# QCopterCAM_LED_Sch.net
KiCad netlist of a schematic drawn in Altium Designer
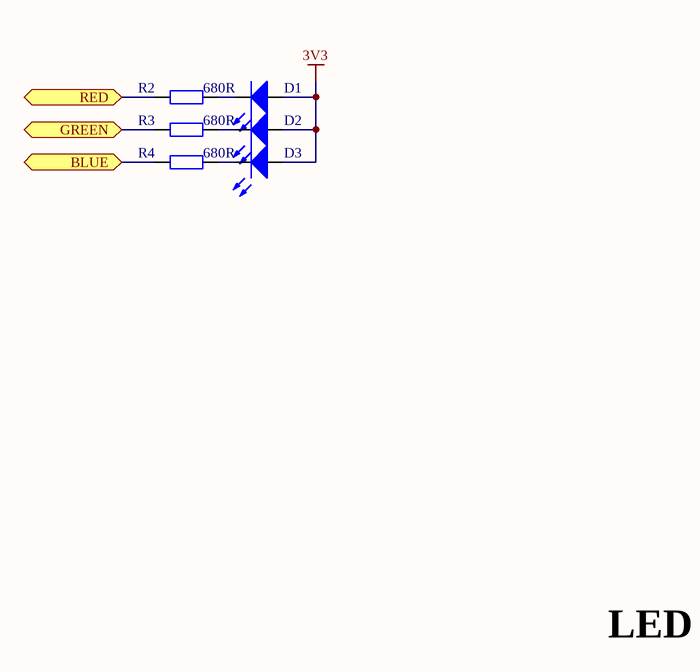
[diagram p0: QCopterCAM_LED_Sch.SchDoc]

(export (version "E")
  (design (tool "Eeschema 10.0.6"))
  (components
    (comp (ref "D1")
      (value "LED_0603_RED")
      (footprint "PCB_Active:LED_0603_RED")
      (description "LED")
      (libsource (lib "SCH_Active") (part "LED_0603_RED"))
    )
    (comp (ref "D2")
      (value "LED_0603_GREEN")
      (footprint "PCB_Active:LED_0603_GREEN")
      (description "LED")
      (libsource (lib "SCH_Active") (part "LED_0603_GREEN"))
    )
    (comp (ref "D3")
      (value "LED_0603_BLUE")
      (footprint "PCB_Active:LED_0603_BLUE")
      (description "LED")
      (libsource (lib "SCH_Active") (part "LED_0603_BLUE"))
    )
    (comp (ref "R2")
      (value "680R")
      (footprint "PCB_Passive:RES_0603")
      (description "Resistor")
      (fields (field (name "Comment") "Res_0603"))
      (libsource (lib "SCH_Passive") (part "Res_0603"))
    )
    (comp (ref "R3")
      (value "680R")
      (footprint "PCB_Passive:RES_0603")
      (description "Resistor")
      (fields (field (name "Comment") "Res_0603"))
      (libsource (lib "SCH_Passive") (part "Res_0603"))
    )
    (comp (ref "R4")
      (value "680R")
      (footprint "PCB_Passive:RES_0603")
      (description "Resistor")
      (fields (field (name "Comment") "Res_0603"))
      (libsource (lib "SCH_Passive") (part "Res_0603"))
    )
  )
  (nets
    (net (code "1") (name "/BLUE") (class "Default")
      (node (ref "R4") (pin "1") (pinfunction "1_1") (pintype "passive"))
    )
    (net (code "2") (name "/GREEN") (class "Default")
      (node (ref "R3") (pin "1") (pinfunction "1_1") (pintype "passive"))
    )
    (net (code "3") (name "/RED") (class "Default")
      (node (ref "R2") (pin "1") (pinfunction "1_1") (pintype "passive"))
    )
    (net (code "4") (name "3V3") (class "Default")
      (node (ref "D1") (pin "1") (pinfunction "A_1") (pintype "passive"))
      (node (ref "D2") (pin "1") (pinfunction "A_1") (pintype "passive"))
      (node (ref "D3") (pin "1") (pinfunction "A_1") (pintype "passive"))
    )
    (net (code "5") (name "Net-(D1-K)") (class "Default")
      (node (ref "D1") (pin "2") (pinfunction "K_2") (pintype "passive"))
      (node (ref "R2") (pin "2") (pinfunction "2_2") (pintype "passive"))
    )
    (net (code "6") (name "Net-(D2-K)") (class "Default")
      (node (ref "D2") (pin "2") (pinfunction "K_2") (pintype "passive"))
      (node (ref "R3") (pin "2") (pinfunction "2_2") (pintype "passive"))
    )
    (net (code "7") (name "Net-(D3-K)") (class "Default")
      (node (ref "D3") (pin "2") (pinfunction "K_2") (pintype "passive"))
      (node (ref "R4") (pin "2") (pinfunction "2_2") (pintype "passive"))
    )
  )
)
